# SCH_Audrino_7Seg_2026-09-07.net
KiCad netlist of a schematic drawn in EasyEDA
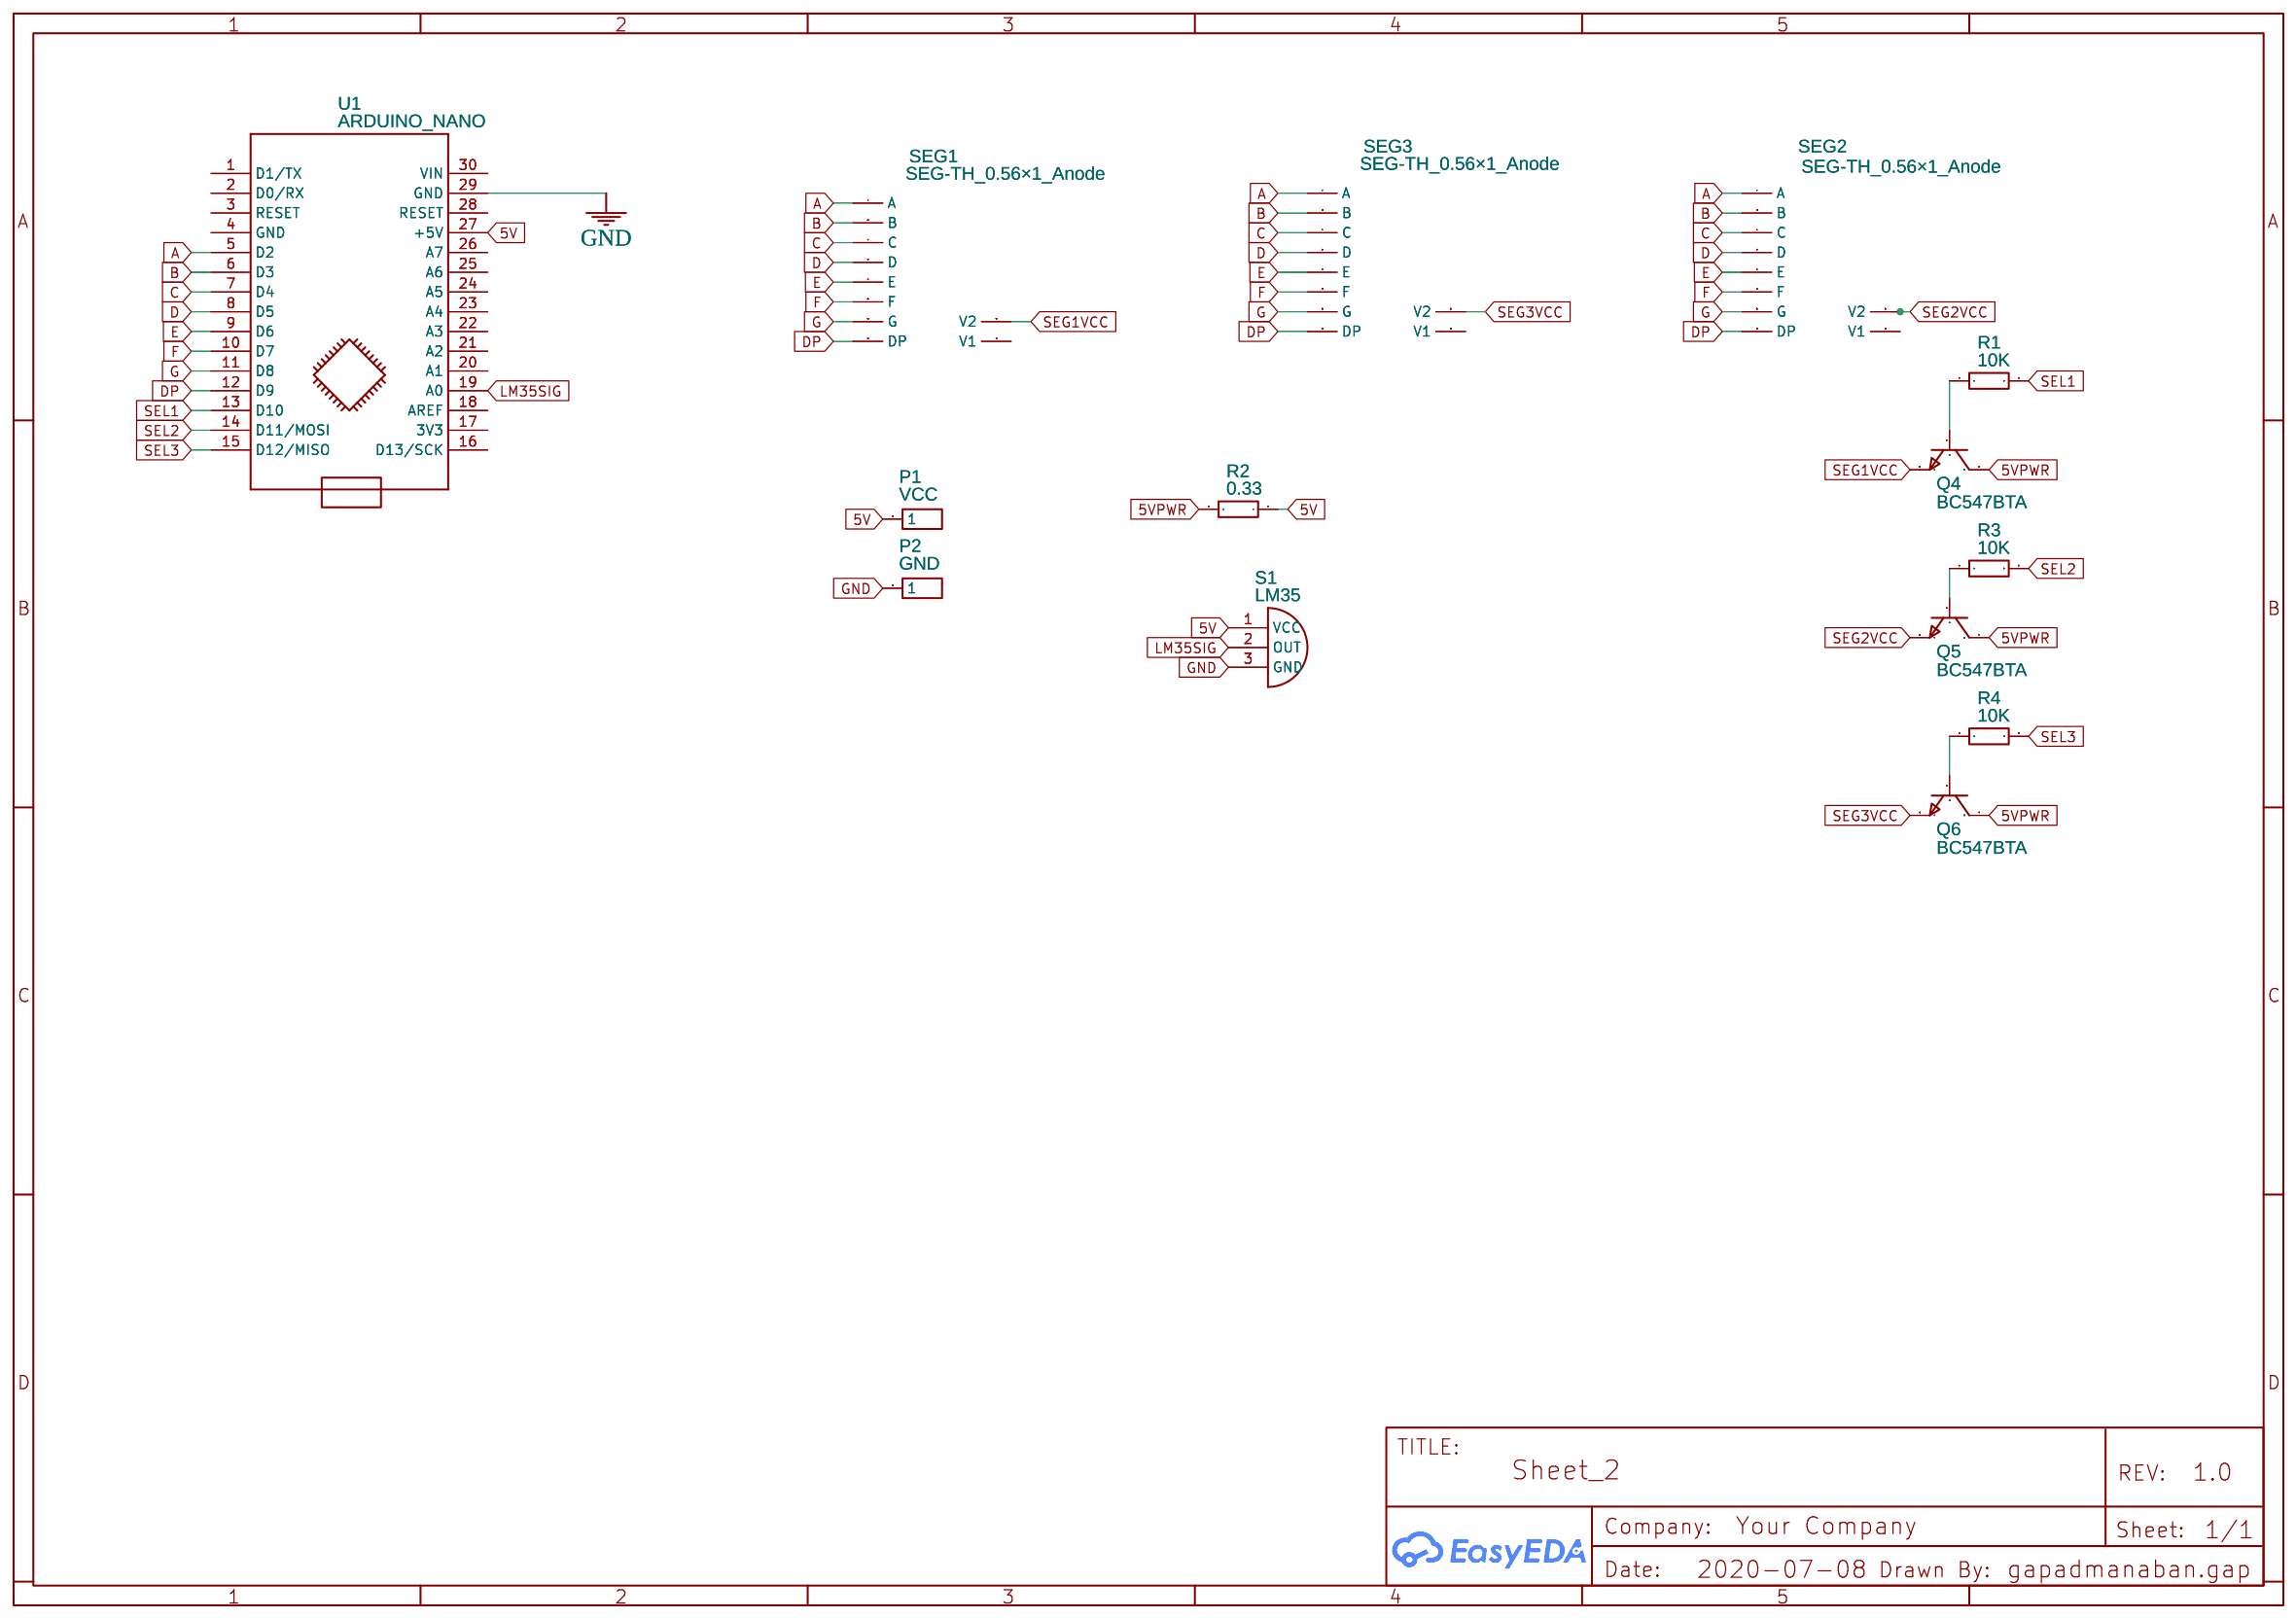
[diagram p0: schematic sheet]

(export (version "E")
  (design (tool "Eeschema 10.0.6"))
  (components
    (comp (ref "P1")
      (value "VCC")
      (fields
        (field (name "Manufacturer Part") "Header-Male-2.54_1x1")
        (field (name "Manufacturer") "ReliaPro")
      )
      (libsource (lib "") (part "Header-Male-2.54_1x1"))
    )
    (comp (ref "P2")
      (value "GND")
      (fields
        (field (name "Manufacturer Part") "Header-Male-2.54_1x1")
        (field (name "Manufacturer") "ReliaPro")
      )
      (libsource (lib "") (part "Header-Male-2.54_1x1"))
    )
    (comp (ref "Q4")
      (value "BC547BTA")
      (fields (field (name "Manufacturer") "ON Semicon"))
      (libsource (lib "") (part "BC547BTA"))
    )
    (comp (ref "Q5")
      (value "BC547BTA")
      (fields (field (name "Manufacturer") "ON Semicon"))
      (libsource (lib "") (part "BC547BTA"))
    )
    (comp (ref "Q6")
      (value "BC547BTA")
      (fields (field (name "Manufacturer") "ON Semicon"))
      (libsource (lib "") (part "BC547BTA"))
    )
    (comp (ref "R1")
      (value "10K")
      (fields (field (name "Manufacturer Part") "MO2WS-0R33±5%-6T63") (field (name "Manufacturer") "FlyWin"))
      (libsource (lib "") (part "MO2WS-0R33±5%-6T63"))
    )
    (comp (ref "R2")
      (value "0.33")
      (fields (field (name "Manufacturer Part") "MO2WS-0R33±5%-6T63") (field (name "Manufacturer") "FlyWin"))
      (libsource (lib "") (part "MO2WS-0R33±5%-6T63_1"))
    )
    (comp (ref "R3")
      (value "10K")
      (fields (field (name "Manufacturer Part") "MO2WS-0R33±5%-6T63") (field (name "Manufacturer") "FlyWin"))
      (libsource (lib "") (part "MO2WS-0R33±5%-6T63"))
    )
    (comp (ref "R4")
      (value "10K")
      (fields (field (name "Manufacturer Part") "MO2WS-0R33±5%-6T63") (field (name "Manufacturer") "FlyWin"))
      (libsource (lib "") (part "MO2WS-0R33±5%-6T63"))
    )
    (comp (ref "S1")
      (value "LM35")
      (fields (field (name "Manufacturer Part") "?"))
      (libsource (lib "") (part "Unknown_635_-485"))
    )
    (comp (ref "SEG1")
      (value "SEG-TH_0.56×1_Anode")
      (fields (field (name "Manufacturer") "志浩"))
      (libsource (lib "") (part "SEG-TH_0.56×1_Anode"))
    )
    (comp (ref "SEG2")
      (value "SEG-TH_0.56×1_Anode")
      (fields (field (name "Manufacturer") "志浩"))
      (libsource (lib "") (part "SEG-TH_0.56×1_Anode"))
    )
    (comp (ref "SEG3")
      (value "SEG-TH_0.56×1_Anode")
      (fields (field (name "Manufacturer") "志浩"))
      (libsource (lib "") (part "SEG-TH_0.56×1_Anode"))
    )
    (comp (ref "U1") (value "ARDUINO_NANO") (libsource (lib "") (part "ARDUINO_NANO")))
  )
  (nets
    (net (code "1") (name "5V") (class "Default")
      (node (ref "P1") (pin "1") (pinfunction "1_1") (pintype "input"))
      (node (ref "R2") (pin "1") (pinfunction "1_1") (pintype "unspecified"))
      (node (ref "S1") (pin "1") (pinfunction "VCC_1") (pintype "unspecified"))
      (node (ref "U1") (pin "27") (pinfunction "+5V_27") (pintype "unspecified"))
    )
    (net (code "2") (name "5VPWR") (class "Default")
      (node (ref "Q4") (pin "1") (pinfunction "C_1") (pintype "unspecified"))
      (node (ref "Q5") (pin "1") (pinfunction "C_1") (pintype "unspecified"))
      (node (ref "Q6") (pin "1") (pinfunction "C_1") (pintype "unspecified"))
      (node (ref "R2") (pin "2") (pinfunction "2_2") (pintype "unspecified"))
    )
    (net (code "3") (name "A") (class "Default")
      (node (ref "SEG1") (pin "7") (pinfunction "A_7") (pintype "unspecified"))
      (node (ref "SEG2") (pin "7") (pinfunction "A_7") (pintype "unspecified"))
      (node (ref "SEG3") (pin "7") (pinfunction "A_7") (pintype "unspecified"))
      (node (ref "U1") (pin "5") (pinfunction "D2_5") (pintype "unspecified"))
    )
    (net (code "4") (name "B") (class "Default")
      (node (ref "SEG1") (pin "6") (pinfunction "B_6") (pintype "unspecified"))
      (node (ref "SEG2") (pin "6") (pinfunction "B_6") (pintype "unspecified"))
      (node (ref "SEG3") (pin "6") (pinfunction "B_6") (pintype "unspecified"))
      (node (ref "U1") (pin "6") (pinfunction "D3_6") (pintype "unspecified"))
    )
    (net (code "5") (name "C") (class "Default")
      (node (ref "SEG1") (pin "4") (pinfunction "C_4") (pintype "unspecified"))
      (node (ref "SEG2") (pin "4") (pinfunction "C_4") (pintype "unspecified"))
      (node (ref "SEG3") (pin "4") (pinfunction "C_4") (pintype "unspecified"))
      (node (ref "U1") (pin "7") (pinfunction "D4_7") (pintype "unspecified"))
    )
    (net (code "6") (name "D") (class "Default")
      (node (ref "SEG1") (pin "2") (pinfunction "D_2") (pintype "unspecified"))
      (node (ref "SEG2") (pin "2") (pinfunction "D_2") (pintype "unspecified"))
      (node (ref "SEG3") (pin "2") (pinfunction "D_2") (pintype "unspecified"))
      (node (ref "U1") (pin "8") (pinfunction "D5_8") (pintype "unspecified"))
    )
    (net (code "7") (name "DP") (class "Default")
      (node (ref "SEG1") (pin "5") (pinfunction "DP_5") (pintype "unspecified"))
      (node (ref "SEG2") (pin "5") (pinfunction "DP_5") (pintype "unspecified"))
      (node (ref "SEG3") (pin "5") (pinfunction "DP_5") (pintype "unspecified"))
      (node (ref "U1") (pin "12") (pinfunction "D9_12") (pintype "unspecified"))
    )
    (net (code "8") (name "E") (class "Default")
      (node (ref "SEG1") (pin "1") (pinfunction "E_1") (pintype "unspecified"))
      (node (ref "SEG2") (pin "1") (pinfunction "E_1") (pintype "unspecified"))
      (node (ref "SEG3") (pin "1") (pinfunction "E_1") (pintype "unspecified"))
      (node (ref "U1") (pin "9") (pinfunction "D6_9") (pintype "unspecified"))
    )
    (net (code "9") (name "F") (class "Default")
      (node (ref "SEG1") (pin "9") (pinfunction "F_9") (pintype "unspecified"))
      (node (ref "SEG2") (pin "9") (pinfunction "F_9") (pintype "unspecified"))
      (node (ref "SEG3") (pin "9") (pinfunction "F_9") (pintype "unspecified"))
      (node (ref "U1") (pin "10") (pinfunction "D7_10") (pintype "unspecified"))
    )
    (net (code "10") (name "G") (class "Default")
      (node (ref "SEG1") (pin "10") (pinfunction "G_10") (pintype "unspecified"))
      (node (ref "SEG2") (pin "10") (pinfunction "G_10") (pintype "unspecified"))
      (node (ref "SEG3") (pin "10") (pinfunction "G_10") (pintype "unspecified"))
      (node (ref "U1") (pin "11") (pinfunction "D8_11") (pintype "unspecified"))
    )
    (net (code "11") (name "GND") (class "Default")
      (node (ref "P2") (pin "1") (pinfunction "1_1") (pintype "input"))
      (node (ref "S1") (pin "3") (pinfunction "GND_3") (pintype "unspecified"))
      (node (ref "U1") (pin "29") (pinfunction "GND_29") (pintype "unspecified"))
    )
    (net (code "12") (name "LM35SIG") (class "Default")
      (node (ref "S1") (pin "2") (pinfunction "OUT_2") (pintype "unspecified"))
      (node (ref "U1") (pin "19") (pinfunction "A0_19") (pintype "unspecified"))
    )
    (net (code "13") (name "Net-(Q4-B)") (class "Default")
      (node (ref "Q4") (pin "2") (pinfunction "B_2") (pintype "unspecified"))
      (node (ref "R1") (pin "1") (pinfunction "1_1") (pintype "unspecified"))
    )
    (net (code "14") (name "Net-(Q5-B)") (class "Default")
      (node (ref "Q5") (pin "2") (pinfunction "B_2") (pintype "unspecified"))
      (node (ref "R3") (pin "1") (pinfunction "1_1") (pintype "unspecified"))
    )
    (net (code "15") (name "Net-(Q6-B)") (class "Default")
      (node (ref "Q6") (pin "2") (pinfunction "B_2") (pintype "unspecified"))
      (node (ref "R4") (pin "1") (pinfunction "1_1") (pintype "unspecified"))
    )
    (net (code "16") (name "SEG1VCC") (class "Default")
      (node (ref "Q4") (pin "3") (pinfunction "E_3") (pintype "unspecified"))
      (node (ref "SEG1") (pin "8") (pinfunction "V2_8") (pintype "unspecified"))
    )
    (net (code "17") (name "SEG2VCC") (class "Default")
      (node (ref "Q5") (pin "3") (pinfunction "E_3") (pintype "unspecified"))
      (node (ref "SEG2") (pin "8") (pinfunction "V2_8") (pintype "unspecified"))
    )
    (net (code "18") (name "SEG3VCC") (class "Default")
      (node (ref "Q6") (pin "3") (pinfunction "E_3") (pintype "unspecified"))
      (node (ref "SEG3") (pin "8") (pinfunction "V2_8") (pintype "unspecified"))
    )
    (net (code "19") (name "SEL1") (class "Default")
      (node (ref "R1") (pin "2") (pinfunction "2_2") (pintype "unspecified"))
      (node (ref "U1") (pin "13") (pinfunction "D10_13") (pintype "unspecified"))
    )
    (net (code "20") (name "SEL2") (class "Default")
      (node (ref "R3") (pin "2") (pinfunction "2_2") (pintype "unspecified"))
      (node (ref "U1") (pin "14") (pinfunction "D11/MOSI_14") (pintype "unspecified"))
    )
    (net (code "21") (name "SEL3") (class "Default")
      (node (ref "R4") (pin "2") (pinfunction "2_2") (pintype "unspecified"))
      (node (ref "U1") (pin "15") (pinfunction "D12/MISO_15") (pintype "unspecified"))
    )
    (net (code "22") (name "unconnected-(SEG1-V1-Pad3)") (class "Default")
      (node (ref "SEG1") (pin "3") (pinfunction "V1_3") (pintype "unspecified"))
    )
    (net (code "23") (name "unconnected-(SEG2-V1-Pad3)") (class "Default")
      (node (ref "SEG2") (pin "3") (pinfunction "V1_3") (pintype "unspecified"))
    )
    (net (code "24") (name "unconnected-(SEG3-V1-Pad3)") (class "Default")
      (node (ref "SEG3") (pin "3") (pinfunction "V1_3") (pintype "unspecified"))
    )
    (net (code "25") (name "unconnected-(U1-3V3-Pad17)") (class "Default")
      (node (ref "U1") (pin "17") (pinfunction "3V3_17") (pintype "unspecified"))
    )
    (net (code "26") (name "unconnected-(U1-A1-Pad20)") (class "Default")
      (node (ref "U1") (pin "20") (pinfunction "A1_20") (pintype "unspecified"))
    )
    (net (code "27") (name "unconnected-(U1-A2-Pad21)") (class "Default")
      (node (ref "U1") (pin "21") (pinfunction "A2_21") (pintype "unspecified"))
    )
    (net (code "28") (name "unconnected-(U1-A3-Pad22)") (class "Default")
      (node (ref "U1") (pin "22") (pinfunction "A3_22") (pintype "unspecified"))
    )
    (net (code "29") (name "unconnected-(U1-A4-Pad23)") (class "Default")
      (node (ref "U1") (pin "23") (pinfunction "A4_23") (pintype "unspecified"))
    )
    (net (code "30") (name "unconnected-(U1-A5-Pad24)") (class "Default")
      (node (ref "U1") (pin "24") (pinfunction "A5_24") (pintype "unspecified"))
    )
    (net (code "31") (name "unconnected-(U1-A6-Pad25)") (class "Default")
      (node (ref "U1") (pin "25") (pinfunction "A6_25") (pintype "unspecified"))
    )
    (net (code "32") (name "unconnected-(U1-A7-Pad26)") (class "Default")
      (node (ref "U1") (pin "26") (pinfunction "A7_26") (pintype "unspecified"))
    )
    (net (code "33") (name "unconnected-(U1-AREF-Pad18)") (class "Default")
      (node (ref "U1") (pin "18") (pinfunction "AREF_18") (pintype "unspecified"))
    )
    (net (code "34") (name "unconnected-(U1-D0{slash}RX-Pad2)") (class "Default")
      (node (ref "U1") (pin "2") (pinfunction "D0/RX_2") (pintype "unspecified"))
    )
    (net (code "35") (name "unconnected-(U1-D1{slash}TX-Pad1)") (class "Default")
      (node (ref "U1") (pin "1") (pinfunction "D1/TX_1") (pintype "unspecified"))
    )
    (net (code "36") (name "unconnected-(U1-D13{slash}SCK-Pad16)") (class "Default")
      (node (ref "U1") (pin "16") (pinfunction "D13/SCK_16") (pintype "unspecified"))
    )
    (net (code "37") (name "unconnected-(U1-GND-Pad4)") (class "Default")
      (node (ref "U1") (pin "4") (pinfunction "GND_4") (pintype "unspecified"))
    )
    (net (code "38") (name "unconnected-(U1-RESET-Pad3)") (class "Default")
      (node (ref "U1") (pin "3") (pinfunction "RESET_3") (pintype "unspecified"))
    )
    (net (code "39") (name "unconnected-(U1-RESET-Pad28)") (class "Default")
      (node (ref "U1") (pin "28") (pinfunction "RESET_28") (pintype "unspecified"))
    )
    (net (code "40") (name "unconnected-(U1-VIN-Pad30)") (class "Default")
      (node (ref "U1") (pin "30") (pinfunction "VIN_30") (pintype "unspecified"))
    )
  )
)
